# dabpi_v1.net
KiCad netlist of a schematic drawn in EAGLE
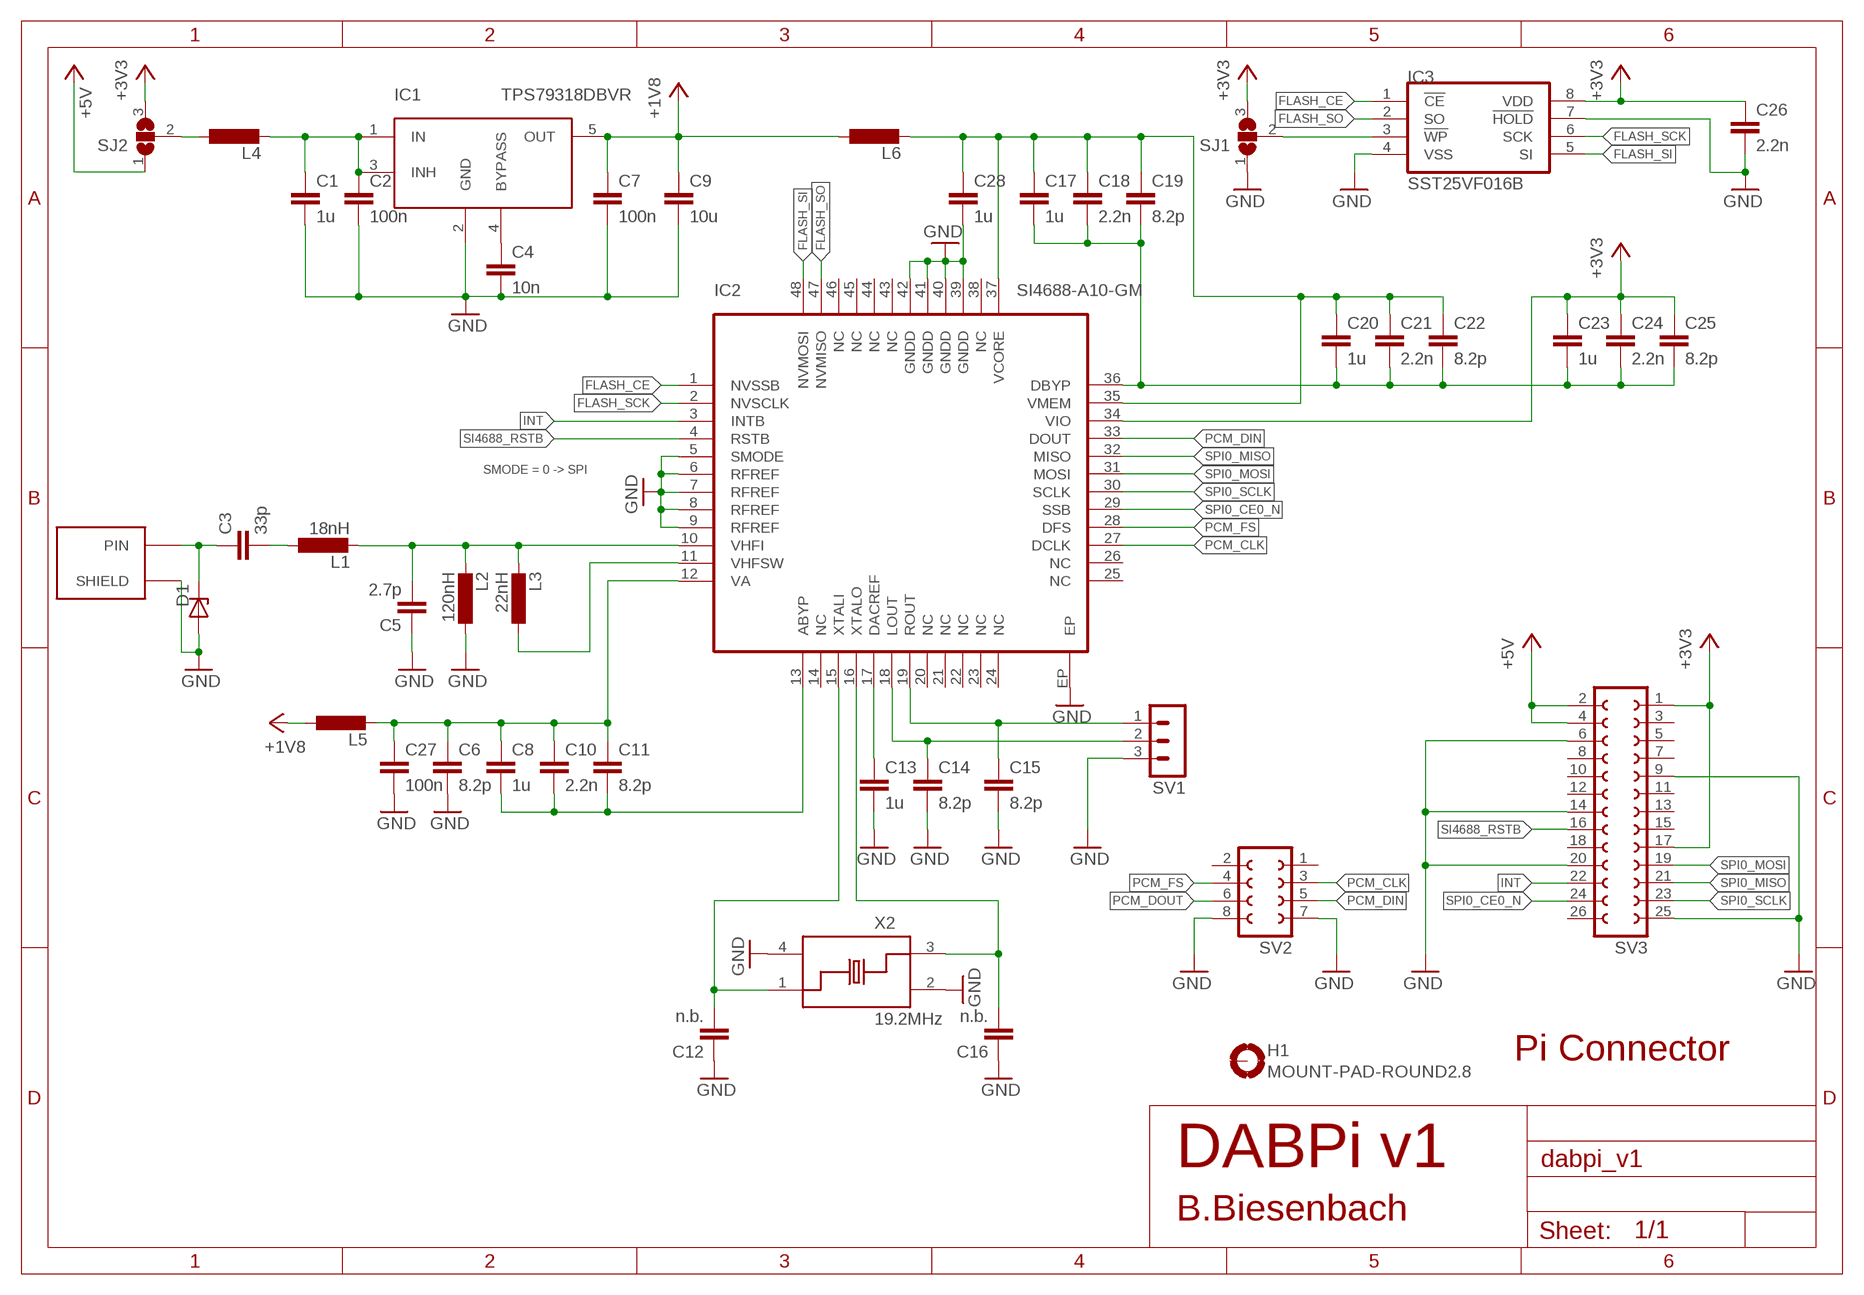
[diagram p0: schematic, sheet 1]

(export (version "E")
  (design (tool "Eeschema 10.0.6"))
  (components
    (comp (ref "C1")
      (value "1u")
      (footprint "eagle-import:SMD0603")
      (libsource (lib "eagle-import") (part "C0603"))
    )
    (comp (ref "C2")
      (value "100n")
      (footprint "eagle-import:SMD0603")
      (libsource (lib "eagle-import") (part "C0603"))
    )
    (comp (ref "C3")
      (value "33p")
      (footprint "eagle-import:SMD0402")
      (libsource (lib "eagle-import") (part "C0402"))
    )
    (comp (ref "C4")
      (value "10n")
      (footprint "eagle-import:SMD0603")
      (libsource (lib "eagle-import") (part "C0603"))
    )
    (comp (ref "C5")
      (value "2.7p")
      (footprint "eagle-import:SMD0402")
      (libsource (lib "eagle-import") (part "C0402"))
    )
    (comp (ref "C6")
      (value "8.2p")
      (footprint "eagle-import:SMD0603")
      (libsource (lib "eagle-import") (part "C0603"))
    )
    (comp (ref "C7")
      (value "100n")
      (footprint "eagle-import:SMD0603")
      (libsource (lib "eagle-import") (part "C0603"))
    )
    (comp (ref "C8")
      (value "1u")
      (footprint "eagle-import:SMD0603")
      (libsource (lib "eagle-import") (part "C0603"))
    )
    (comp (ref "C9")
      (value "10u")
      (footprint "eagle-import:SMD0603")
      (libsource (lib "eagle-import") (part "C0603"))
    )
    (comp (ref "C10")
      (value "2.2n")
      (footprint "eagle-import:SMD0603")
      (libsource (lib "eagle-import") (part "C0603"))
    )
    (comp (ref "C11")
      (value "8.2p")
      (footprint "eagle-import:SMD0603")
      (libsource (lib "eagle-import") (part "C0603"))
    )
    (comp (ref "C12")
      (value "n.b.")
      (footprint "eagle-import:SMD0402")
      (libsource (lib "eagle-import") (part "C0402"))
    )
    (comp (ref "C13")
      (value "1u")
      (footprint "eagle-import:SMD0603")
      (libsource (lib "eagle-import") (part "C0603"))
    )
    (comp (ref "C14")
      (value "8.2p")
      (footprint "eagle-import:SMD0603")
      (libsource (lib "eagle-import") (part "C0603"))
    )
    (comp (ref "C15")
      (value "8.2p")
      (footprint "eagle-import:SMD0603")
      (libsource (lib "eagle-import") (part "C0603"))
    )
    (comp (ref "C16")
      (value "n.b.")
      (footprint "eagle-import:SMD0402")
      (libsource (lib "eagle-import") (part "C0402"))
    )
    (comp (ref "C17")
      (value "1u")
      (footprint "eagle-import:SMD0603")
      (libsource (lib "eagle-import") (part "C0603"))
    )
    (comp (ref "C18")
      (value "2.2n")
      (footprint "eagle-import:SMD0603")
      (libsource (lib "eagle-import") (part "C0603"))
    )
    (comp (ref "C19")
      (value "8.2p")
      (footprint "eagle-import:SMD0603")
      (libsource (lib "eagle-import") (part "C0603"))
    )
    (comp (ref "C20")
      (value "1u")
      (footprint "eagle-import:SMD0603")
      (libsource (lib "eagle-import") (part "C0603"))
    )
    (comp (ref "C21")
      (value "2.2n")
      (footprint "eagle-import:SMD0603")
      (libsource (lib "eagle-import") (part "C0603"))
    )
    (comp (ref "C22")
      (value "8.2p")
      (footprint "eagle-import:SMD0603")
      (libsource (lib "eagle-import") (part "C0603"))
    )
    (comp (ref "C23")
      (value "1u")
      (footprint "eagle-import:SMD0603")
      (libsource (lib "eagle-import") (part "C0603"))
    )
    (comp (ref "C24")
      (value "2.2n")
      (footprint "eagle-import:SMD0603")
      (libsource (lib "eagle-import") (part "C0603"))
    )
    (comp (ref "C25")
      (value "8.2p")
      (footprint "eagle-import:SMD0603")
      (libsource (lib "eagle-import") (part "C0603"))
    )
    (comp (ref "C26")
      (value "2.2n")
      (footprint "eagle-import:SMD0603")
      (libsource (lib "eagle-import") (part "C0603"))
    )
    (comp (ref "C27")
      (value "100n")
      (footprint "eagle-import:SMD0603")
      (libsource (lib "eagle-import") (part "C0603"))
    )
    (comp (ref "C28")
      (value "1u")
      (footprint "eagle-import:SMD0603")
      (libsource (lib "eagle-import") (part "C0603"))
    )
    (comp (ref "D1")
      (value "ESD9L5.0")
      (footprint "eagle-import:SOD923")
      (libsource (lib "eagle-import") (part "ESD9L5.0"))
    )
    (comp (ref "H1")
      (value "MOUNT-PAD-ROUND2.8")
      (footprint "eagle-import:2,8-PAD")
      (libsource (lib "eagle-import") (part "MOUNT-PAD-ROUND2.8"))
    )
    (comp (ref "IC1")
      (value "TPS79318DBVR")
      (footprint "eagle-import:SOT23-5")
      (libsource (lib "eagle-import") (part "TPS79318DBVR"))
    )
    (comp (ref "IC2")
      (value "SI4688-A10-GM")
      (footprint "eagle-import:QFN48")
      (libsource (lib "eagle-import") (part "SI4688-A10-GM"))
    )
    (comp (ref "IC3")
      (value "SST25VF016B")
      (footprint "eagle-import:SO08")
      (libsource (lib "eagle-import") (part "SST25VF016B"))
    )
    (comp (ref "L1")
      (value "18nH")
      (footprint "eagle-import:SMD0402")
      (libsource (lib "eagle-import") (part "L0402"))
    )
    (comp (ref "L2")
      (value "120nH")
      (footprint "eagle-import:SMD0402")
      (libsource (lib "eagle-import") (part "L0402"))
    )
    (comp (ref "L3")
      (value "22nH")
      (footprint "eagle-import:SMD0402")
      (libsource (lib "eagle-import") (part "L0402"))
    )
    (comp (ref "L4")
      (value "L0603")
      (footprint "eagle-import:SMD0603")
      (libsource (lib "eagle-import") (part "L0603"))
    )
    (comp (ref "L5")
      (value "L0603")
      (footprint "eagle-import:SMD0603")
      (libsource (lib "eagle-import") (part "L0603"))
    )
    (comp (ref "L6")
      (value "L0603")
      (footprint "eagle-import:SMD0603")
      (libsource (lib "eagle-import") (part "L0603"))
    )
    (comp (ref "SJ1")
      (value "SJ2W")
      (footprint "eagle-import:SJ_2")
      (libsource (lib "eagle-import") (part "SJ2W"))
    )
    (comp (ref "SJ2")
      (value "SJ2W")
      (footprint "eagle-import:SJ_2")
      (libsource (lib "eagle-import") (part "SJ2W"))
    )
    (comp (ref "SV1")
      (value "MA03-1")
      (footprint "eagle-import:MA03-1")
      (libsource (lib "eagle-import") (part "MA03-1"))
    )
    (comp (ref "SV2")
      (value "FE04-2")
      (footprint "eagle-import:FE04-2")
      (libsource (lib "eagle-import") (part "FE04-2"))
    )
    (comp (ref "SV3")
      (value "FE13-2")
      (footprint "eagle-import:FE13-2")
      (libsource (lib "eagle-import") (part "FE13-2"))
    )
    (comp (ref "X1")
      (value "SMA_LP_1.57MM")
      (footprint "eagle-import:SMA_LP_1.57MM")
      (libsource (lib "eagle-import") (part "SMA_LP_1.57MM"))
    )
    (comp (ref "X2")
      (value "19.2MHz")
      (footprint "eagle-import:XTAL_3.2X2.5")
      (libsource (lib "eagle-import") (part "XTAL_3.2X2.5"))
    )
  )
  (nets
    (net (code "1") (name "+1V8") (class "Default")
      (node (ref "C7") (pin "1") (pinfunction "1_1") (pintype "passive"))
      (node (ref "C9") (pin "1") (pinfunction "1_1") (pintype "passive"))
      (node (ref "IC1") (pin "5") (pinfunction "OUT_5") (pintype "power_in"))
      (node (ref "L5") (pin "1") (pinfunction "1_1") (pintype "passive"))
      (node (ref "L6") (pin "1") (pinfunction "1_1") (pintype "passive"))
    )
    (net (code "2") (name "+3V3") (class "Default")
      (node (ref "C23") (pin "1") (pinfunction "1_1") (pintype "passive"))
      (node (ref "C24") (pin "1") (pinfunction "1_1") (pintype "passive"))
      (node (ref "C25") (pin "1") (pinfunction "1_1") (pintype "passive"))
      (node (ref "C26") (pin "1") (pinfunction "1_1") (pintype "passive"))
      (node (ref "IC2") (pin "34") (pinfunction "VIO_34") (pintype "power_in"))
      (node (ref "IC3") (pin "8") (pinfunction "VDD_8") (pintype "power_in"))
      (node (ref "SJ1") (pin "3") (pinfunction "3_3") (pintype "passive"))
      (node (ref "SJ2") (pin "3") (pinfunction "3_3") (pintype "passive"))
      (node (ref "SV3") (pin "1") (pinfunction "1_1") (pintype "passive"))
      (node (ref "SV3") (pin "17") (pinfunction "17_17") (pintype "passive"))
    )
    (net (code "3") (name "+5V") (class "Default")
      (node (ref "SJ2") (pin "1") (pinfunction "1_1") (pintype "passive"))
      (node (ref "SV3") (pin "2") (pinfunction "2_2") (pintype "passive"))
      (node (ref "SV3") (pin "4") (pinfunction "4_4") (pintype "passive"))
    )
    (net (code "4") (name "FLASH_CE") (class "Default")
      (node (ref "IC2") (pin "1") (pinfunction "NVSSB_1") (pintype "output"))
      (node (ref "IC3") (pin "1") (pinfunction "~{CE}_1") (pintype "input"))
    )
    (net (code "5") (name "FLASH_SCK") (class "Default")
      (node (ref "IC2") (pin "2") (pinfunction "NVSCLK_2") (pintype "output"))
      (node (ref "IC3") (pin "6") (pinfunction "SCK_6") (pintype "input"))
    )
    (net (code "6") (name "FLASH_SI") (class "Default")
      (node (ref "IC2") (pin "48") (pinfunction "NVMOSI_48") (pintype "output"))
      (node (ref "IC3") (pin "5") (pinfunction "SI_5") (pintype "input"))
    )
    (net (code "7") (name "FLASH_SO") (class "Default")
      (node (ref "IC2") (pin "47") (pinfunction "NVMISO_47") (pintype "input"))
      (node (ref "IC3") (pin "2") (pinfunction "SO_2") (pintype "output"))
    )
    (net (code "8") (name "GND") (class "Default")
      (node (ref "C1") (pin "2") (pinfunction "2_2") (pintype "passive"))
      (node (ref "C12") (pin "1") (pinfunction "1_1") (pintype "passive"))
      (node (ref "C13") (pin "2") (pinfunction "2_2") (pintype "passive"))
      (node (ref "C14") (pin "2") (pinfunction "2_2") (pintype "passive"))
      (node (ref "C15") (pin "2") (pinfunction "2_2") (pintype "passive"))
      (node (ref "C16") (pin "1") (pinfunction "1_1") (pintype "passive"))
      (node (ref "C2") (pin "2") (pinfunction "2_2") (pintype "passive"))
      (node (ref "C26") (pin "2") (pinfunction "2_2") (pintype "passive"))
      (node (ref "C27") (pin "2") (pinfunction "2_2") (pintype "passive"))
      (node (ref "C28") (pin "2") (pinfunction "2_2") (pintype "passive"))
      (node (ref "C4") (pin "2") (pinfunction "2_2") (pintype "passive"))
      (node (ref "C5") (pin "1") (pinfunction "1_1") (pintype "passive"))
      (node (ref "C6") (pin "2") (pinfunction "2_2") (pintype "passive"))
      (node (ref "C7") (pin "2") (pinfunction "2_2") (pintype "passive"))
      (node (ref "C9") (pin "2") (pinfunction "2_2") (pintype "passive"))
      (node (ref "D1") (pin "A") (pinfunction "A_A") (pintype "passive"))
      (node (ref "IC1") (pin "2") (pinfunction "GND_2") (pintype "power_in"))
      (node (ref "IC2") (pin "39") (pinfunction "GNDD_39") (pintype "power_in"))
      (node (ref "IC2") (pin "40") (pinfunction "GNDD_40") (pintype "power_in"))
      (node (ref "IC2") (pin "41") (pinfunction "GNDD_41") (pintype "power_in"))
      (node (ref "IC2") (pin "42") (pinfunction "GNDD_42") (pintype "power_in"))
      (node (ref "IC2") (pin "5") (pinfunction "SMODE_5") (pintype "input"))
      (node (ref "IC2") (pin "6") (pinfunction "RFREF_6") (pintype "power_in"))
      (node (ref "IC2") (pin "7") (pinfunction "RFREF_7") (pintype "power_in"))
      (node (ref "IC2") (pin "8") (pinfunction "RFREF_8") (pintype "power_in"))
      (node (ref "IC2") (pin "9") (pinfunction "RFREF_9") (pintype "power_in"))
      (node (ref "IC2") (pin "EP") (pinfunction "EP_EP") (pintype "bidirectional"))
      (node (ref "IC3") (pin "4") (pinfunction "VSS_4") (pintype "power_in"))
      (node (ref "IC3") (pin "7") (pinfunction "~{HOLD}_7") (pintype "input"))
      (node (ref "L2") (pin "1") (pinfunction "1_1") (pintype "passive"))
      (node (ref "SJ1") (pin "1") (pinfunction "1_1") (pintype "passive"))
      (node (ref "SV1") (pin "3") (pinfunction "3_3") (pintype "passive"))
      (node (ref "SV2") (pin "7") (pinfunction "7_7") (pintype "passive"))
      (node (ref "SV2") (pin "8") (pinfunction "8_8") (pintype "passive"))
      (node (ref "SV3") (pin "14") (pinfunction "14_14") (pintype "passive"))
      (node (ref "SV3") (pin "20") (pinfunction "20_20") (pintype "passive"))
      (node (ref "SV3") (pin "25") (pinfunction "25_25") (pintype "passive"))
      (node (ref "SV3") (pin "6") (pinfunction "6_6") (pintype "passive"))
      (node (ref "SV3") (pin "9") (pinfunction "9_9") (pintype "passive"))
      (node (ref "X1") (pin "GND") (pinfunction "SHIELD_GND") (pintype "power_in"))
      (node (ref "X1") (pin "GND@1") (pinfunction "SHIELD_GND@1") (pintype "power_in"))
      (node (ref "X1") (pin "GND@2") (pinfunction "SHIELD_GND@2") (pintype "power_in"))
      (node (ref "X1") (pin "GND@3") (pinfunction "SHIELD_GND@3") (pintype "power_in"))
      (node (ref "X2") (pin "2") (pinfunction "GND_2") (pintype "power_in"))
      (node (ref "X2") (pin "4") (pinfunction "GND_4") (pintype "power_in"))
    )
    (net (code "9") (name "INT") (class "Default")
      (node (ref "IC2") (pin "3") (pinfunction "INTB_3") (pintype "output"))
      (node (ref "SV3") (pin "22") (pinfunction "22_22") (pintype "passive"))
    )
    (net (code "10") (name "Net-(C3-Pad2)") (class "Default")
      (node (ref "C3") (pin "2") (pinfunction "2_2") (pintype "passive"))
      (node (ref "L1") (pin "1") (pinfunction "1_1") (pintype "passive"))
    )
    (net (code "11") (name "Net-(D1-C)") (class "Default")
      (node (ref "C3") (pin "1") (pinfunction "1_1") (pintype "passive"))
      (node (ref "D1") (pin "K") (pinfunction "C_K") (pintype "passive"))
      (node (ref "X1") (pin "PIN") (pinfunction "PIN_PIN") (pintype "passive"))
    )
    (net (code "12") (name "Net-(IC1-BYPASS)") (class "Default")
      (node (ref "C4") (pin "1") (pinfunction "1_1") (pintype "passive"))
      (node (ref "IC1") (pin "4") (pinfunction "BYPASS_4") (pintype "power_in"))
    )
    (net (code "13") (name "Net-(IC1-IN)") (class "Default")
      (node (ref "C1") (pin "1") (pinfunction "1_1") (pintype "passive"))
      (node (ref "C2") (pin "1") (pinfunction "1_1") (pintype "passive"))
      (node (ref "IC1") (pin "1") (pinfunction "IN_1") (pintype "power_in"))
      (node (ref "IC1") (pin "3") (pinfunction "INH_3") (pintype "input"))
      (node (ref "L4") (pin "2") (pinfunction "2_2") (pintype "passive"))
    )
    (net (code "14") (name "Net-(IC2-ABYP)") (class "Default")
      (node (ref "C10") (pin "2") (pinfunction "2_2") (pintype "passive"))
      (node (ref "C11") (pin "2") (pinfunction "2_2") (pintype "passive"))
      (node (ref "C8") (pin "2") (pinfunction "2_2") (pintype "passive"))
      (node (ref "IC2") (pin "13") (pinfunction "ABYP_13") (pintype "power_in"))
    )
    (net (code "15") (name "Net-(IC2-DACREF)") (class "Default")
      (node (ref "C13") (pin "1") (pinfunction "1_1") (pintype "passive"))
      (node (ref "IC2") (pin "17") (pinfunction "DACREF_17") (pintype "power_in"))
    )
    (net (code "16") (name "Net-(IC2-DBYP)") (class "Default")
      (node (ref "C17") (pin "2") (pinfunction "2_2") (pintype "passive"))
      (node (ref "C18") (pin "2") (pinfunction "2_2") (pintype "passive"))
      (node (ref "C19") (pin "2") (pinfunction "2_2") (pintype "passive"))
      (node (ref "C20") (pin "2") (pinfunction "2_2") (pintype "passive"))
      (node (ref "C21") (pin "2") (pinfunction "2_2") (pintype "passive"))
      (node (ref "C22") (pin "2") (pinfunction "2_2") (pintype "passive"))
      (node (ref "C23") (pin "2") (pinfunction "2_2") (pintype "passive"))
      (node (ref "C24") (pin "2") (pinfunction "2_2") (pintype "passive"))
      (node (ref "C25") (pin "2") (pinfunction "2_2") (pintype "passive"))
      (node (ref "IC2") (pin "36") (pinfunction "DBYP_36") (pintype "power_in"))
    )
    (net (code "17") (name "Net-(IC2-LOUT)") (class "Default")
      (node (ref "C14") (pin "1") (pinfunction "1_1") (pintype "passive"))
      (node (ref "IC2") (pin "18") (pinfunction "LOUT_18") (pintype "output"))
      (node (ref "SV1") (pin "2") (pinfunction "2_2") (pintype "passive"))
    )
    (net (code "18") (name "Net-(IC2-ROUT)") (class "Default")
      (node (ref "C15") (pin "1") (pinfunction "1_1") (pintype "passive"))
      (node (ref "IC2") (pin "19") (pinfunction "ROUT_19") (pintype "output"))
      (node (ref "SV1") (pin "1") (pinfunction "1_1") (pintype "passive"))
    )
    (net (code "19") (name "Net-(IC2-VA)") (class "Default")
      (node (ref "C10") (pin "1") (pinfunction "1_1") (pintype "passive"))
      (node (ref "C11") (pin "1") (pinfunction "1_1") (pintype "passive"))
      (node (ref "C27") (pin "1") (pinfunction "1_1") (pintype "passive"))
      (node (ref "C6") (pin "1") (pinfunction "1_1") (pintype "passive"))
      (node (ref "C8") (pin "1") (pinfunction "1_1") (pintype "passive"))
      (node (ref "IC2") (pin "12") (pinfunction "VA_12") (pintype "power_in"))
      (node (ref "L5") (pin "2") (pinfunction "2_2") (pintype "passive"))
    )
    (net (code "20") (name "Net-(IC2-VCORE)") (class "Default")
      (node (ref "C17") (pin "1") (pinfunction "1_1") (pintype "passive"))
      (node (ref "C18") (pin "1") (pinfunction "1_1") (pintype "passive"))
      (node (ref "C19") (pin "1") (pinfunction "1_1") (pintype "passive"))
      (node (ref "C20") (pin "1") (pinfunction "1_1") (pintype "passive"))
      (node (ref "C21") (pin "1") (pinfunction "1_1") (pintype "passive"))
      (node (ref "C22") (pin "1") (pinfunction "1_1") (pintype "passive"))
      (node (ref "C28") (pin "1") (pinfunction "1_1") (pintype "passive"))
      (node (ref "IC2") (pin "35") (pinfunction "VMEM_35") (pintype "power_in"))
      (node (ref "IC2") (pin "37") (pinfunction "VCORE_37") (pintype "power_in"))
      (node (ref "L6") (pin "2") (pinfunction "2_2") (pintype "passive"))
    )
    (net (code "21") (name "Net-(IC2-VHFI)") (class "Default")
      (node (ref "C5") (pin "2") (pinfunction "2_2") (pintype "passive"))
      (node (ref "IC2") (pin "10") (pinfunction "VHFI_10") (pintype "input"))
      (node (ref "L1") (pin "2") (pinfunction "2_2") (pintype "passive"))
      (node (ref "L2") (pin "2") (pinfunction "2_2") (pintype "passive"))
      (node (ref "L3") (pin "2") (pinfunction "2_2") (pintype "passive"))
    )
    (net (code "22") (name "Net-(IC2-VHFSW)") (class "Default")
      (node (ref "IC2") (pin "11") (pinfunction "VHFSW_11") (pintype "output"))
      (node (ref "L3") (pin "1") (pinfunction "1_1") (pintype "passive"))
    )
    (net (code "23") (name "Net-(IC2-XTALI)") (class "Default")
      (node (ref "C12") (pin "2") (pinfunction "2_2") (pintype "passive"))
      (node (ref "IC2") (pin "15") (pinfunction "XTALI_15") (pintype "input"))
      (node (ref "X2") (pin "1") (pinfunction "1_1") (pintype "passive"))
    )
    (net (code "24") (name "Net-(IC2-XTALO)") (class "Default")
      (node (ref "C16") (pin "2") (pinfunction "2_2") (pintype "passive"))
      (node (ref "IC2") (pin "16") (pinfunction "XTALO_16") (pintype "output"))
      (node (ref "X2") (pin "3") (pinfunction "3_3") (pintype "passive"))
    )
    (net (code "25") (name "Net-(IC3-~{WP})") (class "Default")
      (node (ref "IC3") (pin "3") (pinfunction "~{WP}_3") (pintype "input"))
      (node (ref "SJ1") (pin "2") (pinfunction "2_2") (pintype "passive"))
    )
    (net (code "26") (name "Net-(L4-Pad1)") (class "Default")
      (node (ref "L4") (pin "1") (pinfunction "1_1") (pintype "passive"))
      (node (ref "SJ2") (pin "2") (pinfunction "2_2") (pintype "passive"))
    )
    (net (code "27") (name "PCM_CLK") (class "Default")
      (node (ref "IC2") (pin "27") (pinfunction "DCLK_27") (pintype "bidirectional"))
      (node (ref "SV2") (pin "3") (pinfunction "3_3") (pintype "passive"))
    )
    (net (code "28") (name "PCM_DIN") (class "Default")
      (node (ref "IC2") (pin "33") (pinfunction "DOUT_33") (pintype "output"))
      (node (ref "SV2") (pin "5") (pinfunction "5_5") (pintype "passive"))
    )
    (net (code "29") (name "PCM_DOUT") (class "Default")
      (node (ref "SV2") (pin "6") (pinfunction "6_6") (pintype "passive"))
    )
    (net (code "30") (name "PCM_FS") (class "Default")
      (node (ref "IC2") (pin "28") (pinfunction "DFS_28") (pintype "bidirectional"))
      (node (ref "SV2") (pin "4") (pinfunction "4_4") (pintype "passive"))
    )
    (net (code "31") (name "SI4688_RSTB") (class "Default")
      (node (ref "IC2") (pin "4") (pinfunction "RSTB_4") (pintype "input"))
      (node (ref "SV3") (pin "16") (pinfunction "16_16") (pintype "passive"))
    )
    (net (code "32") (name "SPI0_CE0_N") (class "Default")
      (node (ref "IC2") (pin "29") (pinfunction "SSB_29") (pintype "input"))
      (node (ref "SV3") (pin "24") (pinfunction "24_24") (pintype "passive"))
    )
    (net (code "33") (name "SPI0_MISO") (class "Default")
      (node (ref "IC2") (pin "32") (pinfunction "MISO_32") (pintype "bidirectional"))
      (node (ref "SV3") (pin "21") (pinfunction "21_21") (pintype "passive"))
    )
    (net (code "34") (name "SPI0_MOSI") (class "Default")
      (node (ref "IC2") (pin "31") (pinfunction "MOSI_31") (pintype "bidirectional"))
      (node (ref "SV3") (pin "19") (pinfunction "19_19") (pintype "passive"))
    )
    (net (code "35") (name "SPI0_SCLK") (class "Default")
      (node (ref "IC2") (pin "30") (pinfunction "SCLK_30") (pintype "input"))
      (node (ref "SV3") (pin "23") (pinfunction "23_23") (pintype "passive"))
    )
    (net (code "36") (name "unconnected-(H1-MOUNT-PadB2,8)") (class "Default")
      (node (ref "H1") (pin "B2,8") (pinfunction "MOUNT_B2,8") (pintype "passive"))
    )
    (net (code "37") (name "unconnected-(IC2-NC-Pad14)") (class "Default")
      (node (ref "IC2") (pin "14") (pinfunction "NC_14") (pintype "no_connect"))
    )
    (net (code "38") (name "unconnected-(IC2-NC-Pad20)") (class "Default")
      (node (ref "IC2") (pin "20") (pinfunction "NC_20") (pintype "no_connect"))
    )
    (net (code "39") (name "unconnected-(IC2-NC-Pad21)") (class "Default")
      (node (ref "IC2") (pin "21") (pinfunction "NC_21") (pintype "no_connect"))
    )
    (net (code "40") (name "unconnected-(IC2-NC-Pad22)") (class "Default")
      (node (ref "IC2") (pin "22") (pinfunction "NC_22") (pintype "no_connect"))
    )
    (net (code "41") (name "unconnected-(IC2-NC-Pad23)") (class "Default")
      (node (ref "IC2") (pin "23") (pinfunction "NC_23") (pintype "no_connect"))
    )
    (net (code "42") (name "unconnected-(IC2-NC-Pad24)") (class "Default")
      (node (ref "IC2") (pin "24") (pinfunction "NC_24") (pintype "no_connect"))
    )
    (net (code "43") (name "unconnected-(IC2-NC-Pad25)") (class "Default")
      (node (ref "IC2") (pin "25") (pinfunction "NC_25") (pintype "no_connect"))
    )
    (net (code "44") (name "unconnected-(IC2-NC-Pad26)") (class "Default")
      (node (ref "IC2") (pin "26") (pinfunction "NC_26") (pintype "no_connect"))
    )
    (net (code "45") (name "unconnected-(IC2-NC-Pad38)") (class "Default")
      (node (ref "IC2") (pin "38") (pinfunction "NC_38") (pintype "no_connect"))
    )
    (net (code "46") (name "unconnected-(IC2-NC-Pad43)") (class "Default")
      (node (ref "IC2") (pin "43") (pinfunction "NC_43") (pintype "no_connect"))
    )
    (net (code "47") (name "unconnected-(IC2-NC-Pad44)") (class "Default")
      (node (ref "IC2") (pin "44") (pinfunction "NC_44") (pintype "no_connect"))
    )
    (net (code "48") (name "unconnected-(IC2-NC-Pad45)") (class "Default")
      (node (ref "IC2") (pin "45") (pinfunction "NC_45") (pintype "no_connect"))
    )
    (net (code "49") (name "unconnected-(IC2-NC-Pad46)") (class "Default")
      (node (ref "IC2") (pin "46") (pinfunction "NC_46") (pintype "no_connect"))
    )
    (net (code "50") (name "unconnected-(SV2-Pad1)") (class "Default")
      (node (ref "SV2") (pin "1") (pinfunction "1_1") (pintype "passive"))
    )
    (net (code "51") (name "unconnected-(SV2-Pad2)") (class "Default")
      (node (ref "SV2") (pin "2") (pinfunction "2_2") (pintype "passive"))
    )
    (net (code "52") (name "unconnected-(SV3-Pad3)") (class "Default")
      (node (ref "SV3") (pin "3") (pinfunction "3_3") (pintype "passive"))
    )
    (net (code "53") (name "unconnected-(SV3-Pad5)") (class "Default")
      (node (ref "SV3") (pin "5") (pinfunction "5_5") (pintype "passive"))
    )
    (net (code "54") (name "unconnected-(SV3-Pad7)") (class "Default")
      (node (ref "SV3") (pin "7") (pinfunction "7_7") (pintype "passive"))
    )
    (net (code "55") (name "unconnected-(SV3-Pad8)") (class "Default")
      (node (ref "SV3") (pin "8") (pinfunction "8_8") (pintype "passive"))
    )
    (net (code "56") (name "unconnected-(SV3-Pad10)") (class "Default")
      (node (ref "SV3") (pin "10") (pinfunction "10_10") (pintype "passive"))
    )
    (net (code "57") (name "unconnected-(SV3-Pad11)") (class "Default")
      (node (ref "SV3") (pin "11") (pinfunction "11_11") (pintype "passive"))
    )
    (net (code "58") (name "unconnected-(SV3-Pad12)") (class "Default")
      (node (ref "SV3") (pin "12") (pinfunction "12_12") (pintype "passive"))
    )
    (net (code "59") (name "unconnected-(SV3-Pad13)") (class "Default")
      (node (ref "SV3") (pin "13") (pinfunction "13_13") (pintype "passive"))
    )
    (net (code "60") (name "unconnected-(SV3-Pad15)") (class "Default")
      (node (ref "SV3") (pin "15") (pinfunction "15_15") (pintype "passive"))
    )
    (net (code "61") (name "unconnected-(SV3-Pad18)") (class "Default")
      (node (ref "SV3") (pin "18") (pinfunction "18_18") (pintype "passive"))
    )
    (net (code "62") (name "unconnected-(SV3-Pad26)") (class "Default")
      (node (ref "SV3") (pin "26") (pinfunction "26_26") (pintype "passive"))
    )
  )
)
